# Sheet1.net
KiCad netlist of a schematic drawn in Altium Designer
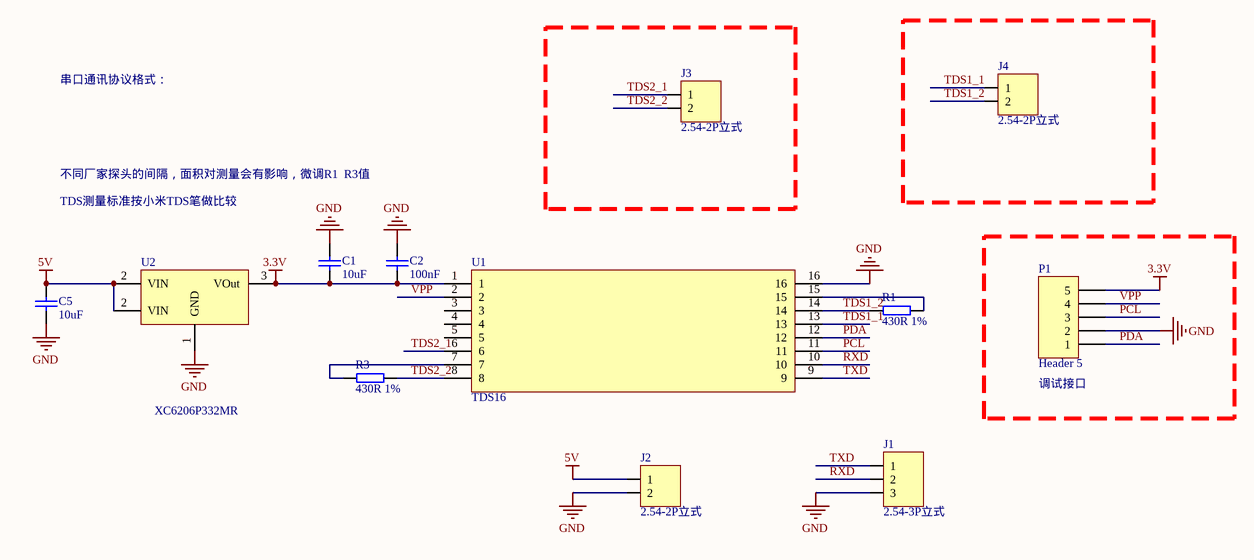
[diagram p0: Sheet1.SchDoc]

(export (version "E")
  (design (tool "Eeschema 10.0.6"))
  (components
    (comp (ref "C1") (value "10uF") (footprint "LC-0603_C") (libsource (lib "LC_LIB") (part "C0603")))
    (comp (ref "C2") (value "100nF") (footprint "LC-0603_C") (libsource (lib "LC_LIB") (part "C0603")))
    (comp (ref "C5") (value "10uF") (footprint "LC-0603_C") (libsource (lib "LC_LIB") (part "C0603")))
    (comp (ref "J1")
      (value "2.54-3P立式")
      (footprint "3P2.54")
      (libsource (lib "Connector_Library1") (part "2.54-3P立式"))
    )
    (comp (ref "J2")
      (value "2.54-2P立式")
      (footprint "2P2.54")
      (libsource (lib "Connector_Library1") (part "2.54-2P立式"))
    )
    (comp (ref "J3")
      (value "2.54-2P立式")
      (footprint "2P2.54")
      (libsource (lib "Connector_Library1") (part "2.54-2P立式"))
    )
    (comp (ref "J4")
      (value "2.54-2P立式")
      (footprint "2P2.54")
      (libsource (lib "Connector_Library1") (part "2.54-2P立式"))
    )
    (comp (ref "P1")
      (value "Header 5")
      (footprint "HDR1X5")
      (description "Header, 5-Pin")
      (fields (field (name "PUBLISHER") "Altium Limited"))
      (libsource (lib "Miscellaneous Connectors") (part "Header 5"))
    )
    (comp (ref "R1") (value "430R 1%") (footprint "LC-0603_R") (libsource (lib "LC_LIB") (part "R0603")))
    (comp (ref "R3") (value "430R 1%") (footprint "LC-0603_R") (libsource (lib "LC_LIB") (part "R0603")))
    (comp (ref "U1")
      (value "TDS16")
      (footprint "LC-SOIC-16_150mil")
      (libsource (lib "LC_LIB") (part "TDS16"))
    )
    (comp (ref "U2")
      (value "XC6206P332MR")
      (footprint "LC-SOT-23(SOT-23-3)")
      (libsource (lib "LC_LIB") (part "HT75XX_SOT89"))
    )
  )
  (nets
    (net (code "1") (name "/PCL") (class "Default")
      (node (ref "P1") (pin "3") (pinfunction "3_3") (pintype "passive"))
      (node (ref "U1") (pin "11") (pinfunction "11_11") (pintype "passive"))
    )
    (net (code "2") (name "/PDA") (class "Default")
      (node (ref "P1") (pin "1") (pinfunction "1_1") (pintype "passive"))
      (node (ref "U1") (pin "12") (pinfunction "12_12") (pintype "passive"))
    )
    (net (code "3") (name "/RXD") (class "Default")
      (node (ref "J1") (pin "2") (pinfunction "2_2") (pintype "passive"))
      (node (ref "U1") (pin "10") (pinfunction "10_10") (pintype "passive"))
    )
    (net (code "4") (name "/TDS1_1") (class "Default")
      (node (ref "J4") (pin "1") (pinfunction "1_1") (pintype "passive"))
      (node (ref "U1") (pin "13") (pinfunction "13_13") (pintype "passive"))
    )
    (net (code "5") (name "/TDS1_2") (class "Default")
      (node (ref "J4") (pin "2") (pinfunction "2_2") (pintype "passive"))
      (node (ref "R1") (pin "2") (pintype "passive"))
      (node (ref "U1") (pin "14") (pinfunction "14_14") (pintype "passive"))
    )
    (net (code "6") (name "/TDS2_1") (class "Default")
      (node (ref "J3") (pin "1") (pinfunction "1_1") (pintype "passive"))
      (node (ref "U1") (pin "6") (pinfunction "6_6") (pintype "passive"))
    )
    (net (code "7") (name "/TDS2_2") (class "Default")
      (node (ref "J3") (pin "2") (pinfunction "2_2") (pintype "passive"))
      (node (ref "R3") (pin "1") (pintype "passive"))
      (node (ref "U1") (pin "8") (pinfunction "8_8") (pintype "passive"))
    )
    (net (code "8") (name "/TXD") (class "Default")
      (node (ref "J1") (pin "1") (pinfunction "1_1") (pintype "passive"))
      (node (ref "U1") (pin "9") (pinfunction "9_9") (pintype "passive"))
    )
    (net (code "9") (name "/VPP") (class "Default")
      (node (ref "P1") (pin "4") (pinfunction "4_4") (pintype "passive"))
      (node (ref "U1") (pin "2") (pinfunction "2_2") (pintype "passive"))
    )
    (net (code "10") (name "3.3V") (class "Default")
      (node (ref "C1") (pin "1") (pinfunction "1_1") (pintype "passive"))
      (node (ref "C2") (pin "1") (pinfunction "1_1") (pintype "passive"))
      (node (ref "P1") (pin "5") (pinfunction "5_5") (pintype "passive"))
      (node (ref "U1") (pin "1") (pinfunction "1_1") (pintype "passive"))
      (node (ref "U2") (pin "3") (pinfunction "VOut_3") (pintype "passive"))
    )
    (net (code "11") (name "5V") (class "Default")
      (node (ref "C5") (pin "2") (pinfunction "2_2") (pintype "passive"))
      (node (ref "J2") (pin "1") (pinfunction "1_1") (pintype "passive"))
      (node (ref "U2") (pin "2") (pinfunction "VIN_2") (pintype "passive"))
    )
    (net (code "12") (name "GND") (class "Default")
      (node (ref "C1") (pin "2") (pinfunction "2_2") (pintype "passive"))
      (node (ref "C2") (pin "2") (pinfunction "2_2") (pintype "passive"))
      (node (ref "C5") (pin "1") (pinfunction "1_1") (pintype "passive"))
      (node (ref "J1") (pin "3") (pinfunction "3_3") (pintype "passive"))
      (node (ref "J2") (pin "2") (pinfunction "2_2") (pintype "passive"))
      (node (ref "P1") (pin "2") (pinfunction "2_2") (pintype "passive"))
      (node (ref "U1") (pin "16") (pinfunction "16_16") (pintype "passive"))
      (node (ref "U2") (pin "1") (pinfunction "GND_1") (pintype "passive"))
    )
    (net (code "13") (name "Net-(R1-Pad1)") (class "Default")
      (node (ref "R1") (pin "1") (pintype "passive"))
      (node (ref "U1") (pin "15") (pinfunction "15_15") (pintype "passive"))
    )
    (net (code "14") (name "Net-(R3-Pad2)") (class "Default")
      (node (ref "R3") (pin "2") (pintype "passive"))
      (node (ref "U1") (pin "7") (pinfunction "7_7") (pintype "passive"))
    )
    (net (code "15") (name "unconnected-(U1-Pad3)") (class "Default")
      (node (ref "U1") (pin "3") (pinfunction "3_3") (pintype "passive"))
    )
    (net (code "16") (name "unconnected-(U1-Pad4)") (class "Default")
      (node (ref "U1") (pin "4") (pinfunction "4_4") (pintype "passive"))
    )
    (net (code "17") (name "unconnected-(U1-Pad5)") (class "Default")
      (node (ref "U1") (pin "5") (pinfunction "5_5") (pintype "passive"))
    )
  )
)
